# VDMEDA_7SegmentDriver.net
KiCad netlist of a schematic drawn in Altium Designer
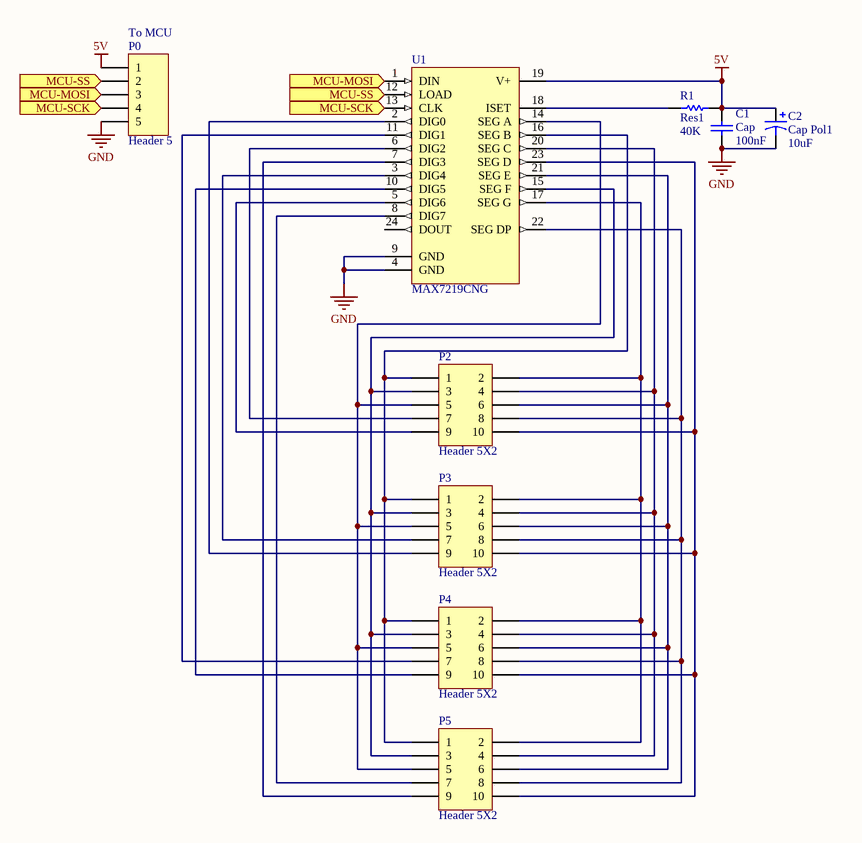
[diagram p0: VDMEDA_7SegmentDriver.SchDoc]

(export (version "E")
  (design (tool "Eeschema 10.0.6"))
  (components
    (comp (ref "C1")
      (value "Cap")
      (footprint "RAD-0.2")
      (description "Capacitor")
      (fields (field (name "ALTIUM_VALUE") "100nF") (field (name "PUBLISHER") "Altium Limited"))
      (libsource (lib "Miscellaneous Devices") (part "Cap"))
    )
    (comp (ref "C2")
      (value "Cap Pol1")
      (footprint "RB5-10.5")
      (description "Polarized Capacitor (Radial)")
      (fields (field (name "ALTIUM_VALUE") "10uF") (field (name "PUBLISHER") "Altium Limited"))
      (libsource (lib "Miscellaneous Devices") (part "Cap Pol1"))
    )
    (comp (ref "P0")
      (value "Header 5")
      (footprint "HDR1X5")
      (description "Header, 5-Pin")
      (fields (field (name "PUBLISHER") "Altium Limited"))
      (libsource (lib "Miscellaneous Connectors") (part "Header 5"))
    )
    (comp (ref "P2")
      (value "Header 5X2")
      (footprint "HDR2X5")
      (description "Header, 5-Pin, Dual row")
      (fields (field (name "PUBLISHER") "Altium Limited"))
      (libsource (lib "Miscellaneous Connectors") (part "Header 5X2"))
    )
    (comp (ref "P3")
      (value "Header 5X2")
      (footprint "HDR2X5")
      (description "Header, 5-Pin, Dual row")
      (fields (field (name "PUBLISHER") "Altium Limited"))
      (libsource (lib "Miscellaneous Connectors") (part "Header 5X2"))
    )
    (comp (ref "P4")
      (value "Header 5X2")
      (footprint "HDR2X5")
      (description "Header, 5-Pin, Dual row")
      (fields (field (name "PUBLISHER") "Altium Limited"))
      (libsource (lib "Miscellaneous Connectors") (part "Header 5X2"))
    )
    (comp (ref "P5")
      (value "Header 5X2")
      (footprint "HDR2X5")
      (description "Header, 5-Pin, Dual row")
      (fields (field (name "PUBLISHER") "Altium Limited"))
      (libsource (lib "Miscellaneous Connectors") (part "Header 5X2"))
    )
    (comp (ref "R1")
      (value "Res1")
      (footprint "AXIAL-0.3")
      (description "Resistor")
      (fields (field (name "ALTIUM_VALUE") "40K") (field (name "PUBLISHER") "Altium Limited"))
      (libsource (lib "Miscellaneous Devices") (part "Res1"))
    )
    (comp (ref "U1")
      (value "MAX7219CNG")
      (footprint "NG24A")
      (description "Serially Interfaced, 8-Digit LED Display Driver")
      (fields (field (name "PUBLISHER") "Altium Limited"))
      (libsource (lib "Maxim Interface Display Driver") (part "MAX7219CNG"))
    )
  )
  (nets
    (net (code "1") (name "/MCU-MOSI") (class "Default")
      (node (ref "P0") (pin "3") (pinfunction "3_3") (pintype "passive"))
      (node (ref "U1") (pin "1") (pinfunction "DIN_1") (pintype "input"))
    )
    (net (code "2") (name "/MCU-SCK") (class "Default")
      (node (ref "P0") (pin "4") (pinfunction "4_4") (pintype "passive"))
      (node (ref "U1") (pin "13") (pinfunction "CLK_13") (pintype "input"))
    )
    (net (code "3") (name "/MCU-SS") (class "Default")
      (node (ref "P0") (pin "2") (pinfunction "2_2") (pintype "passive"))
      (node (ref "U1") (pin "12") (pinfunction "LOAD_12") (pintype "input"))
    )
    (net (code "4") (name "5V") (class "Default")
      (node (ref "C1") (pin "2") (pinfunction "2_2") (pintype "passive"))
      (node (ref "C2") (pin "1") (pinfunction "1_1") (pintype "passive"))
      (node (ref "P0") (pin "1") (pinfunction "1_1") (pintype "passive"))
      (node (ref "R1") (pin "2") (pinfunction "2_2") (pintype "passive"))
      (node (ref "U1") (pin "19") (pinfunction "V+_19") (pintype "power_in"))
    )
    (net (code "5") (name "GND") (class "Default")
      (node (ref "C1") (pin "1") (pinfunction "1_1") (pintype "passive"))
      (node (ref "C2") (pin "2") (pinfunction "2_2") (pintype "passive"))
      (node (ref "P0") (pin "5") (pinfunction "5_5") (pintype "passive"))
      (node (ref "U1") (pin "4") (pinfunction "GND_4") (pintype "power_in"))
      (node (ref "U1") (pin "9") (pinfunction "GND_9") (pintype "power_in"))
    )
    (net (code "6") (name "Net-(U1-DIG0)") (class "Default")
      (node (ref "P3") (pin "9") (pinfunction "9_9") (pintype "passive"))
      (node (ref "U1") (pin "2") (pinfunction "DIG0_2") (pintype "output"))
    )
    (net (code "7") (name "Net-(U1-DIG1)") (class "Default")
      (node (ref "P4") (pin "7") (pinfunction "7_7") (pintype "passive"))
      (node (ref "U1") (pin "11") (pinfunction "DIG1_11") (pintype "output"))
    )
    (net (code "8") (name "Net-(U1-DIG2)") (class "Default")
      (node (ref "P2") (pin "7") (pinfunction "7_7") (pintype "passive"))
      (node (ref "U1") (pin "6") (pinfunction "DIG2_6") (pintype "output"))
    )
    (net (code "9") (name "Net-(U1-DIG3)") (class "Default")
      (node (ref "P5") (pin "9") (pinfunction "9_9") (pintype "passive"))
      (node (ref "U1") (pin "7") (pinfunction "DIG3_7") (pintype "output"))
    )
    (net (code "10") (name "Net-(U1-DIG4)") (class "Default")
      (node (ref "P3") (pin "7") (pinfunction "7_7") (pintype "passive"))
      (node (ref "U1") (pin "3") (pinfunction "DIG4_3") (pintype "output"))
    )
    (net (code "11") (name "Net-(U1-DIG5)") (class "Default")
      (node (ref "P4") (pin "9") (pinfunction "9_9") (pintype "passive"))
      (node (ref "U1") (pin "10") (pinfunction "DIG5_10") (pintype "output"))
    )
    (net (code "12") (name "Net-(U1-DIG6)") (class "Default")
      (node (ref "P2") (pin "9") (pinfunction "9_9") (pintype "passive"))
      (node (ref "U1") (pin "5") (pinfunction "DIG6_5") (pintype "output"))
    )
    (net (code "13") (name "Net-(U1-DIG7)") (class "Default")
      (node (ref "P5") (pin "7") (pinfunction "7_7") (pintype "passive"))
      (node (ref "U1") (pin "8") (pinfunction "DIG7_8") (pintype "output"))
    )
    (net (code "14") (name "Net-(U1-ISET)") (class "Default")
      (node (ref "R1") (pin "1") (pinfunction "1_1") (pintype "passive"))
      (node (ref "U1") (pin "18") (pinfunction "ISET_18") (pintype "passive"))
    )
    (net (code "15") (name "Net-(U1-SEG_A)") (class "Default")
      (node (ref "P2") (pin "5") (pinfunction "5_5") (pintype "passive"))
      (node (ref "P3") (pin "5") (pinfunction "5_5") (pintype "passive"))
      (node (ref "P4") (pin "5") (pinfunction "5_5") (pintype "passive"))
      (node (ref "P5") (pin "5") (pinfunction "5_5") (pintype "passive"))
      (node (ref "U1") (pin "14") (pinfunction "SEG_A_14") (pintype "output"))
    )
    (net (code "16") (name "Net-(U1-SEG_B)") (class "Default")
      (node (ref "P2") (pin "1") (pinfunction "1_1") (pintype "passive"))
      (node (ref "P3") (pin "1") (pinfunction "1_1") (pintype "passive"))
      (node (ref "P4") (pin "1") (pinfunction "1_1") (pintype "passive"))
      (node (ref "P5") (pin "1") (pinfunction "1_1") (pintype "passive"))
      (node (ref "U1") (pin "16") (pinfunction "SEG_B_16") (pintype "output"))
    )
    (net (code "17") (name "Net-(U1-SEG_C)") (class "Default")
      (node (ref "P2") (pin "4") (pinfunction "4_4") (pintype "passive"))
      (node (ref "P3") (pin "4") (pinfunction "4_4") (pintype "passive"))
      (node (ref "P4") (pin "4") (pinfunction "4_4") (pintype "passive"))
      (node (ref "P5") (pin "4") (pinfunction "4_4") (pintype "passive"))
      (node (ref "U1") (pin "20") (pinfunction "SEG_C_20") (pintype "output"))
    )
    (net (code "18") (name "Net-(U1-SEG_D)") (class "Default")
      (node (ref "P2") (pin "10") (pinfunction "10_10") (pintype "passive"))
      (node (ref "P3") (pin "10") (pinfunction "10_10") (pintype "passive"))
      (node (ref "P4") (pin "10") (pinfunction "10_10") (pintype "passive"))
      (node (ref "P5") (pin "10") (pinfunction "10_10") (pintype "passive"))
      (node (ref "U1") (pin "23") (pinfunction "SEG_D_23") (pintype "output"))
    )
    (net (code "19") (name "Net-(U1-SEG_DP)") (class "Default")
      (node (ref "P2") (pin "8") (pinfunction "8_8") (pintype "passive"))
      (node (ref "P3") (pin "8") (pinfunction "8_8") (pintype "passive"))
      (node (ref "P4") (pin "8") (pinfunction "8_8") (pintype "passive"))
      (node (ref "P5") (pin "8") (pinfunction "8_8") (pintype "passive"))
      (node (ref "U1") (pin "22") (pinfunction "SEG_DP_22") (pintype "output"))
    )
    (net (code "20") (name "Net-(U1-SEG_E)") (class "Default")
      (node (ref "P2") (pin "6") (pinfunction "6_6") (pintype "passive"))
      (node (ref "P3") (pin "6") (pinfunction "6_6") (pintype "passive"))
      (node (ref "P4") (pin "6") (pinfunction "6_6") (pintype "passive"))
      (node (ref "P5") (pin "6") (pinfunction "6_6") (pintype "passive"))
      (node (ref "U1") (pin "21") (pinfunction "SEG_E_21") (pintype "output"))
    )
    (net (code "21") (name "Net-(U1-SEG_F)") (class "Default")
      (node (ref "P2") (pin "3") (pinfunction "3_3") (pintype "passive"))
      (node (ref "P3") (pin "3") (pinfunction "3_3") (pintype "passive"))
      (node (ref "P4") (pin "3") (pinfunction "3_3") (pintype "passive"))
      (node (ref "P5") (pin "3") (pinfunction "3_3") (pintype "passive"))
      (node (ref "U1") (pin "15") (pinfunction "SEG_F_15") (pintype "output"))
    )
    (net (code "22") (name "Net-(U1-SEG_G)") (class "Default")
      (node (ref "P2") (pin "2") (pinfunction "2_2") (pintype "passive"))
      (node (ref "P3") (pin "2") (pinfunction "2_2") (pintype "passive"))
      (node (ref "P4") (pin "2") (pinfunction "2_2") (pintype "passive"))
      (node (ref "P5") (pin "2") (pinfunction "2_2") (pintype "passive"))
      (node (ref "U1") (pin "17") (pinfunction "SEG_G_17") (pintype "output"))
    )
    (net (code "23") (name "unconnected-(U1-DOUT-Pad24)") (class "Default")
      (node (ref "U1") (pin "24") (pinfunction "DOUT_24") (pintype "output"))
    )
  )
)
